# SOLARPANELCONN.net
KiCad netlist of a schematic drawn in EAGLE
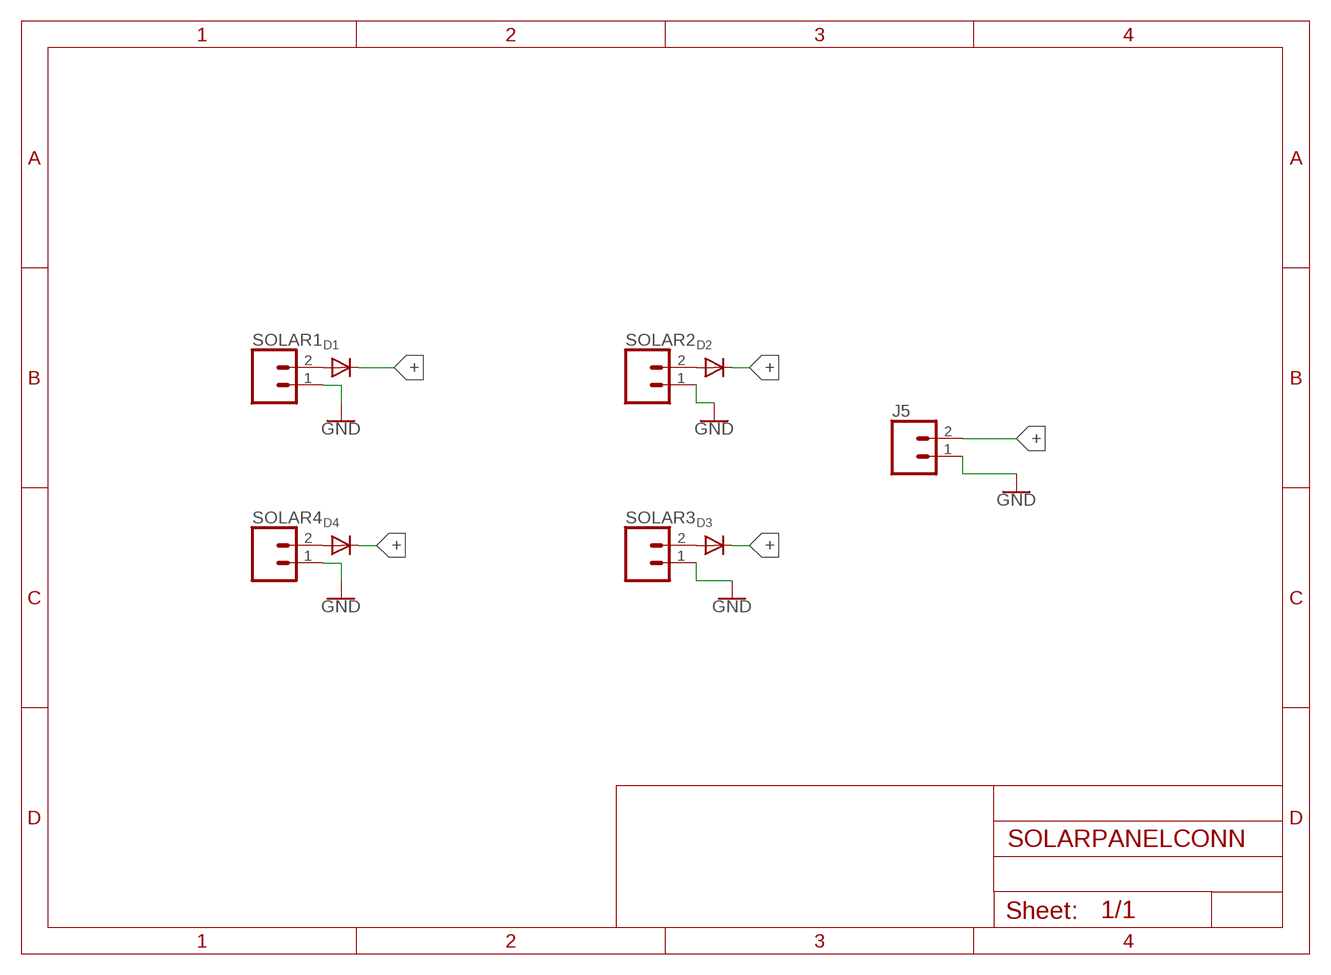
[diagram p0: schematic, sheet 1]

(export (version "E")
  (design (tool "Eeschema 10.0.6"))
  (components
    (comp (ref "D1")
      (value "DIODESOD-123")
      (footprint "eagle-import:SOD-123")
      (libsource (lib "eagle-import") (part "DIODESOD-123"))
    )
    (comp (ref "D2")
      (value "DIODESOD-123")
      (footprint "eagle-import:SOD-123")
      (libsource (lib "eagle-import") (part "DIODESOD-123"))
    )
    (comp (ref "D3")
      (value "DIODESOD-123")
      (footprint "eagle-import:SOD-123")
      (libsource (lib "eagle-import") (part "DIODESOD-123"))
    )
    (comp (ref "D4")
      (value "DIODESOD-123")
      (footprint "eagle-import:SOD-123")
      (libsource (lib "eagle-import") (part "DIODESOD-123"))
    )
    (comp (ref "J5")
      (value "CONN_02")
      (footprint "eagle-import:1X02")
      (libsource (lib "eagle-import") (part "CONN_02"))
    )
    (comp (ref "SOLAR1")
      (value "CONN_02")
      (footprint "eagle-import:1X02")
      (libsource (lib "eagle-import") (part "CONN_02"))
    )
    (comp (ref "SOLAR2")
      (value "CONN_02")
      (footprint "eagle-import:1X02")
      (libsource (lib "eagle-import") (part "CONN_02"))
    )
    (comp (ref "SOLAR3")
      (value "CONN_02")
      (footprint "eagle-import:1X02")
      (libsource (lib "eagle-import") (part "CONN_02"))
    )
    (comp (ref "SOLAR4")
      (value "CONN_02")
      (footprint "eagle-import:1X02")
      (libsource (lib "eagle-import") (part "CONN_02"))
    )
  )
  (nets
    (net (code "1") (name "+") (class "Default")
      (node (ref "D1") (pin "C") (pinfunction "C_C") (pintype "passive"))
      (node (ref "D2") (pin "C") (pinfunction "C_C") (pintype "passive"))
      (node (ref "D3") (pin "C") (pinfunction "C_C") (pintype "passive"))
      (node (ref "D4") (pin "C") (pinfunction "C_C") (pintype "passive"))
      (node (ref "J5") (pin "2") (pinfunction "2_2") (pintype "passive"))
    )
    (net (code "2") (name "GND") (class "Default")
      (node (ref "J5") (pin "1") (pinfunction "1_1") (pintype "passive"))
      (node (ref "SOLAR1") (pin "1") (pinfunction "1_1") (pintype "passive"))
      (node (ref "SOLAR2") (pin "1") (pinfunction "1_1") (pintype "passive"))
      (node (ref "SOLAR3") (pin "1") (pinfunction "1_1") (pintype "passive"))
      (node (ref "SOLAR4") (pin "1") (pinfunction "1_1") (pintype "passive"))
    )
    (net (code "3") (name "Net-(D1-PadA)") (class "Default")
      (node (ref "D1") (pin "A") (pinfunction "A_A") (pintype "passive"))
      (node (ref "SOLAR1") (pin "2") (pinfunction "2_2") (pintype "passive"))
    )
    (net (code "4") (name "Net-(D2-PadA)") (class "Default")
      (node (ref "D2") (pin "A") (pinfunction "A_A") (pintype "passive"))
      (node (ref "SOLAR2") (pin "2") (pinfunction "2_2") (pintype "passive"))
    )
    (net (code "5") (name "Net-(D3-PadA)") (class "Default")
      (node (ref "D3") (pin "A") (pinfunction "A_A") (pintype "passive"))
      (node (ref "SOLAR3") (pin "2") (pinfunction "2_2") (pintype "passive"))
    )
    (net (code "6") (name "Net-(D4-PadA)") (class "Default")
      (node (ref "D4") (pin "A") (pinfunction "A_A") (pintype "passive"))
      (node (ref "SOLAR4") (pin "2") (pinfunction "2_2") (pintype "passive"))
    )
  )
)
